# RTC.net
KiCad netlist of a schematic drawn in Altium Designer
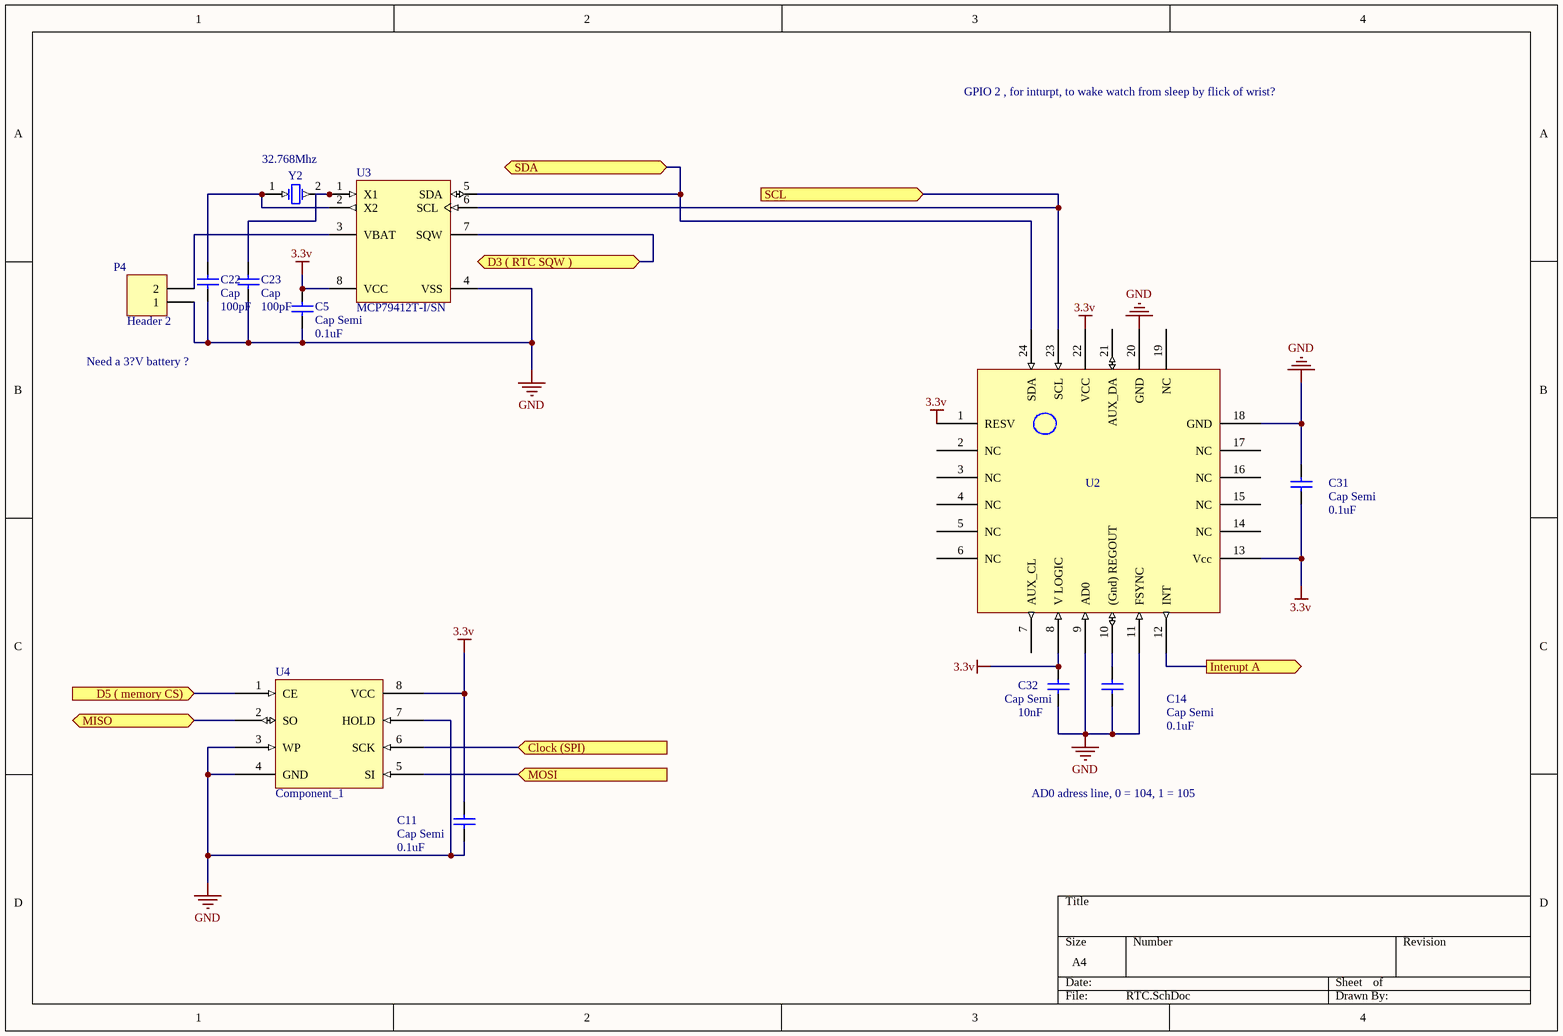
[diagram p0: RTC.SchDoc]

(export (version "E")
  (design (tool "Eeschema 10.0.6"))
  (components
    (comp (ref "C5")
      (value "Cap Semi")
      (footprint "C1206")
      (description "Capacitor (Semiconductor SIM Model)")
      (fields (field (name "ALTIUM_VALUE") "0.1uF") (field (name "PUBLISHER") "Altium Limited"))
      (libsource (lib "Miscellaneous Devices") (part "Cap Semi"))
    )
    (comp (ref "C11")
      (value "Cap Semi")
      (footprint "C1206")
      (description "Capacitor (Semiconductor SIM Model)")
      (fields (field (name "ALTIUM_VALUE") "0.1uF") (field (name "PUBLISHER") "Altium Limited"))
      (libsource (lib "Miscellaneous Devices") (part "Cap Semi"))
    )
    (comp (ref "C14")
      (value "Cap Semi")
      (footprint "C1206")
      (description "Capacitor (Semiconductor SIM Model)")
      (fields (field (name "ALTIUM_VALUE") "0.1uF") (field (name "PUBLISHER") "Altium Limited"))
      (libsource (lib "Miscellaneous Devices") (part "Cap Semi"))
    )
    (comp (ref "C22")
      (value "Cap")
      (footprint "C1206")
      (description "Capacitor")
      (fields (field (name "ALTIUM_VALUE") "100pF") (field (name "PUBLISHER") "Altium Limited"))
      (libsource (lib "Miscellaneous Devices") (part "Cap"))
    )
    (comp (ref "C23")
      (value "Cap")
      (footprint "C1206")
      (description "Capacitor")
      (fields (field (name "ALTIUM_VALUE") "100pF") (field (name "PUBLISHER") "Altium Limited"))
      (libsource (lib "Miscellaneous Devices") (part "Cap"))
    )
    (comp (ref "C31")
      (value "Cap Semi")
      (footprint "C1206")
      (description "Capacitor (Semiconductor SIM Model)")
      (fields (field (name "ALTIUM_VALUE") "0.1uF") (field (name "PUBLISHER") "Altium Limited"))
      (libsource (lib "Miscellaneous Devices") (part "Cap Semi"))
    )
    (comp (ref "C32")
      (value "Cap Semi")
      (footprint "C1206")
      (description "Capacitor (Semiconductor SIM Model)")
      (fields (field (name "ALTIUM_VALUE") "10nF") (field (name "PUBLISHER") "Altium Limited"))
      (libsource (lib "Miscellaneous Devices") (part "Cap Semi"))
    )
    (comp (ref "P4")
      (value "Header 2")
      (footprint "HDR1X2")
      (description "Header, 2-Pin")
      (fields (field (name "PUBLISHER") "Altium Limited"))
      (libsource (lib "Miscellaneous Connectors") (part "Header 2"))
    )
    (comp (ref "U2")
      (value "Component_1")
      (footprint "MPU-9255")
      (libsource (lib "MPU-9255") (part "Component_1"))
    )
    (comp (ref "U3")
      (value "MCP79412T-I/SN")
      (footprint "SOIC-SN8_N")
      (fields (field (name "MANUFACTURER") "Microchip"))
      (libsource (lib "Microchip Interface") (part "MCP79412T-I/SN"))
    )
    (comp (ref "U4")
      (value "Component_1")
      (footprint "SOP8")
      (libsource (lib "SST26VF064B") (part "Component_1"))
    )
    (comp (ref "Y2")
      (value "32.768Mhz")
      (footprint "R38")
      (description "Crystal Oscillator")
      (fields (field (name "PUBLISHER") "Altium Limited"))
      (libsource (lib "Miscellaneous Devices") (part "XTAL"))
    )
  )
  (nets
    (net (code "1") (name "/Clock (SPI)") (class "Default")
      (node (ref "U4") (pin "6") (pinfunction "SCK_6") (pintype "input"))
    )
    (net (code "2") (name "/D3 ( RTC SQW )") (class "Default")
      (node (ref "U3") (pin "7") (pinfunction "SQW_7") (pintype "open_collector"))
    )
    (net (code "3") (name "/D5 ( memory CS)") (class "Default")
      (node (ref "U4") (pin "1") (pinfunction "CE_1") (pintype "input"))
    )
    (net (code "4") (name "/Interupt A") (class "Default")
      (node (ref "U2") (pin "12") (pinfunction "INT_12") (pintype "output"))
    )
    (net (code "5") (name "/MISO") (class "Default")
      (node (ref "U4") (pin "2") (pinfunction "SO_2") (pintype "bidirectional"))
    )
    (net (code "6") (name "/MOSI") (class "Default")
      (node (ref "U4") (pin "5") (pinfunction "SI_5") (pintype "input"))
    )
    (net (code "7") (name "/SCL") (class "Default")
      (node (ref "U2") (pin "23") (pinfunction "SCL_23") (pintype "input"))
      (node (ref "U3") (pin "6") (pinfunction "SCL_6") (pintype "input"))
    )
    (net (code "8") (name "/SDA") (class "Default")
      (node (ref "U2") (pin "24") (pinfunction "SDA_24") (pintype "input"))
      (node (ref "U3") (pin "5") (pinfunction "SDA_5") (pintype "bidirectional"))
    )
    (net (code "9") (name "3.3v") (class "Default")
      (node (ref "C11") (pin "2") (pinfunction "2_2") (pintype "passive"))
      (node (ref "C31") (pin "1") (pinfunction "1_1") (pintype "passive"))
      (node (ref "C32") (pin "2") (pinfunction "2_2") (pintype "passive"))
      (node (ref "C5") (pin "2") (pinfunction "2_2") (pintype "passive"))
      (node (ref "U2") (pin "1") (pinfunction "RESV_1") (pintype "passive"))
      (node (ref "U2") (pin "13") (pinfunction "Vcc_13") (pintype "power_in"))
      (node (ref "U2") (pin "22") (pinfunction "VCC_22") (pintype "power_in"))
      (node (ref "U2") (pin "8") (pinfunction "V_LOGIC_8") (pintype "input"))
      (node (ref "U3") (pin "8") (pinfunction "VCC_8") (pintype "power_in"))
      (node (ref "U4") (pin "8") (pinfunction "VCC_8") (pintype "power_in"))
    )
    (net (code "10") (name "GND") (class "Default")
      (node (ref "C11") (pin "1") (pinfunction "1_1") (pintype "passive"))
      (node (ref "C14") (pin "1") (pinfunction "1_1") (pintype "passive"))
      (node (ref "C22") (pin "1") (pinfunction "1_1") (pintype "passive"))
      (node (ref "C23") (pin "1") (pinfunction "1_1") (pintype "passive"))
      (node (ref "C31") (pin "2") (pinfunction "2_2") (pintype "passive"))
      (node (ref "C32") (pin "1") (pinfunction "1_1") (pintype "passive"))
      (node (ref "C5") (pin "1") (pinfunction "1_1") (pintype "passive"))
      (node (ref "P4") (pin "1") (pinfunction "1_1") (pintype "passive"))
      (node (ref "U2") (pin "11") (pinfunction "FSYNC_11") (pintype "input"))
      (node (ref "U2") (pin "18") (pinfunction "GND_18") (pintype "power_in"))
      (node (ref "U2") (pin "20") (pinfunction "GND_20") (pintype "power_in"))
      (node (ref "U2") (pin "9") (pinfunction "AD0_9") (pintype "input"))
      (node (ref "U3") (pin "4") (pinfunction "VSS_4") (pintype "power_in"))
      (node (ref "U4") (pin "3") (pinfunction "WP_3") (pintype "input"))
      (node (ref "U4") (pin "4") (pinfunction "GND_4") (pintype "power_in"))
      (node (ref "U4") (pin "7") (pinfunction "HOLD_7") (pintype "input"))
    )
    (net (code "11") (name "Net-(U2-(Gnd)_REGOUT)") (class "Default")
      (node (ref "C14") (pin "2") (pinfunction "2_2") (pintype "passive"))
      (node (ref "U2") (pin "10") (pinfunction "(Gnd)_REGOUT_10") (pintype "bidirectional"))
    )
    (net (code "12") (name "Net-(U3-VBAT)") (class "Default")
      (node (ref "P4") (pin "2") (pinfunction "2_2") (pintype "passive"))
      (node (ref "U3") (pin "3") (pinfunction "VBAT_3") (pintype "power_in"))
    )
    (net (code "13") (name "Net-(U3-X1)") (class "Default")
      (node (ref "C23") (pin "2") (pinfunction "2_2") (pintype "passive"))
      (node (ref "U3") (pin "1") (pinfunction "X1_1") (pintype "input"))
      (node (ref "Y2") (pin "2") (pinfunction "OSC2_2") (pintype "output"))
    )
    (net (code "14") (name "Net-(U3-X2)") (class "Default")
      (node (ref "C22") (pin "2") (pinfunction "2_2") (pintype "passive"))
      (node (ref "U3") (pin "2") (pinfunction "X2_2") (pintype "output"))
      (node (ref "Y2") (pin "1") (pinfunction "OSC1_1") (pintype "input"))
    )
    (net (code "15") (name "unconnected-(U2-AUX_CL-Pad7)") (class "Default")
      (node (ref "U2") (pin "7") (pinfunction "AUX_CL_7") (pintype "output"))
    )
    (net (code "16") (name "unconnected-(U2-AUX_DA-Pad21)") (class "Default")
      (node (ref "U2") (pin "21") (pinfunction "AUX_DA_21") (pintype "bidirectional"))
    )
    (net (code "17") (name "unconnected-(U2-NC-Pad2)") (class "Default")
      (node (ref "U2") (pin "2") (pinfunction "NC_2") (pintype "passive"))
    )
    (net (code "18") (name "unconnected-(U2-NC-Pad3)") (class "Default")
      (node (ref "U2") (pin "3") (pinfunction "NC_3") (pintype "passive"))
    )
    (net (code "19") (name "unconnected-(U2-NC-Pad4)") (class "Default")
      (node (ref "U2") (pin "4") (pinfunction "NC_4") (pintype "passive"))
    )
    (net (code "20") (name "unconnected-(U2-NC-Pad5)") (class "Default")
      (node (ref "U2") (pin "5") (pinfunction "NC_5") (pintype "passive"))
    )
    (net (code "21") (name "unconnected-(U2-NC-Pad6)") (class "Default")
      (node (ref "U2") (pin "6") (pinfunction "NC_6") (pintype "passive"))
    )
    (net (code "22") (name "unconnected-(U2-NC-Pad14)") (class "Default")
      (node (ref "U2") (pin "14") (pinfunction "NC_14") (pintype "passive"))
    )
    (net (code "23") (name "unconnected-(U2-NC-Pad15)") (class "Default")
      (node (ref "U2") (pin "15") (pinfunction "NC_15") (pintype "power_in"))
    )
    (net (code "24") (name "unconnected-(U2-NC-Pad16)") (class "Default")
      (node (ref "U2") (pin "16") (pinfunction "NC_16") (pintype "passive"))
    )
    (net (code "25") (name "unconnected-(U2-NC-Pad17)") (class "Default")
      (node (ref "U2") (pin "17") (pinfunction "NC_17") (pintype "passive"))
    )
    (net (code "26") (name "unconnected-(U2-NC-Pad19)") (class "Default")
      (node (ref "U2") (pin "19") (pinfunction "NC_19") (pintype "passive"))
    )
  )
)
